# Extrudrboard.net
KiCad netlist of a schematic drawn in EAGLE
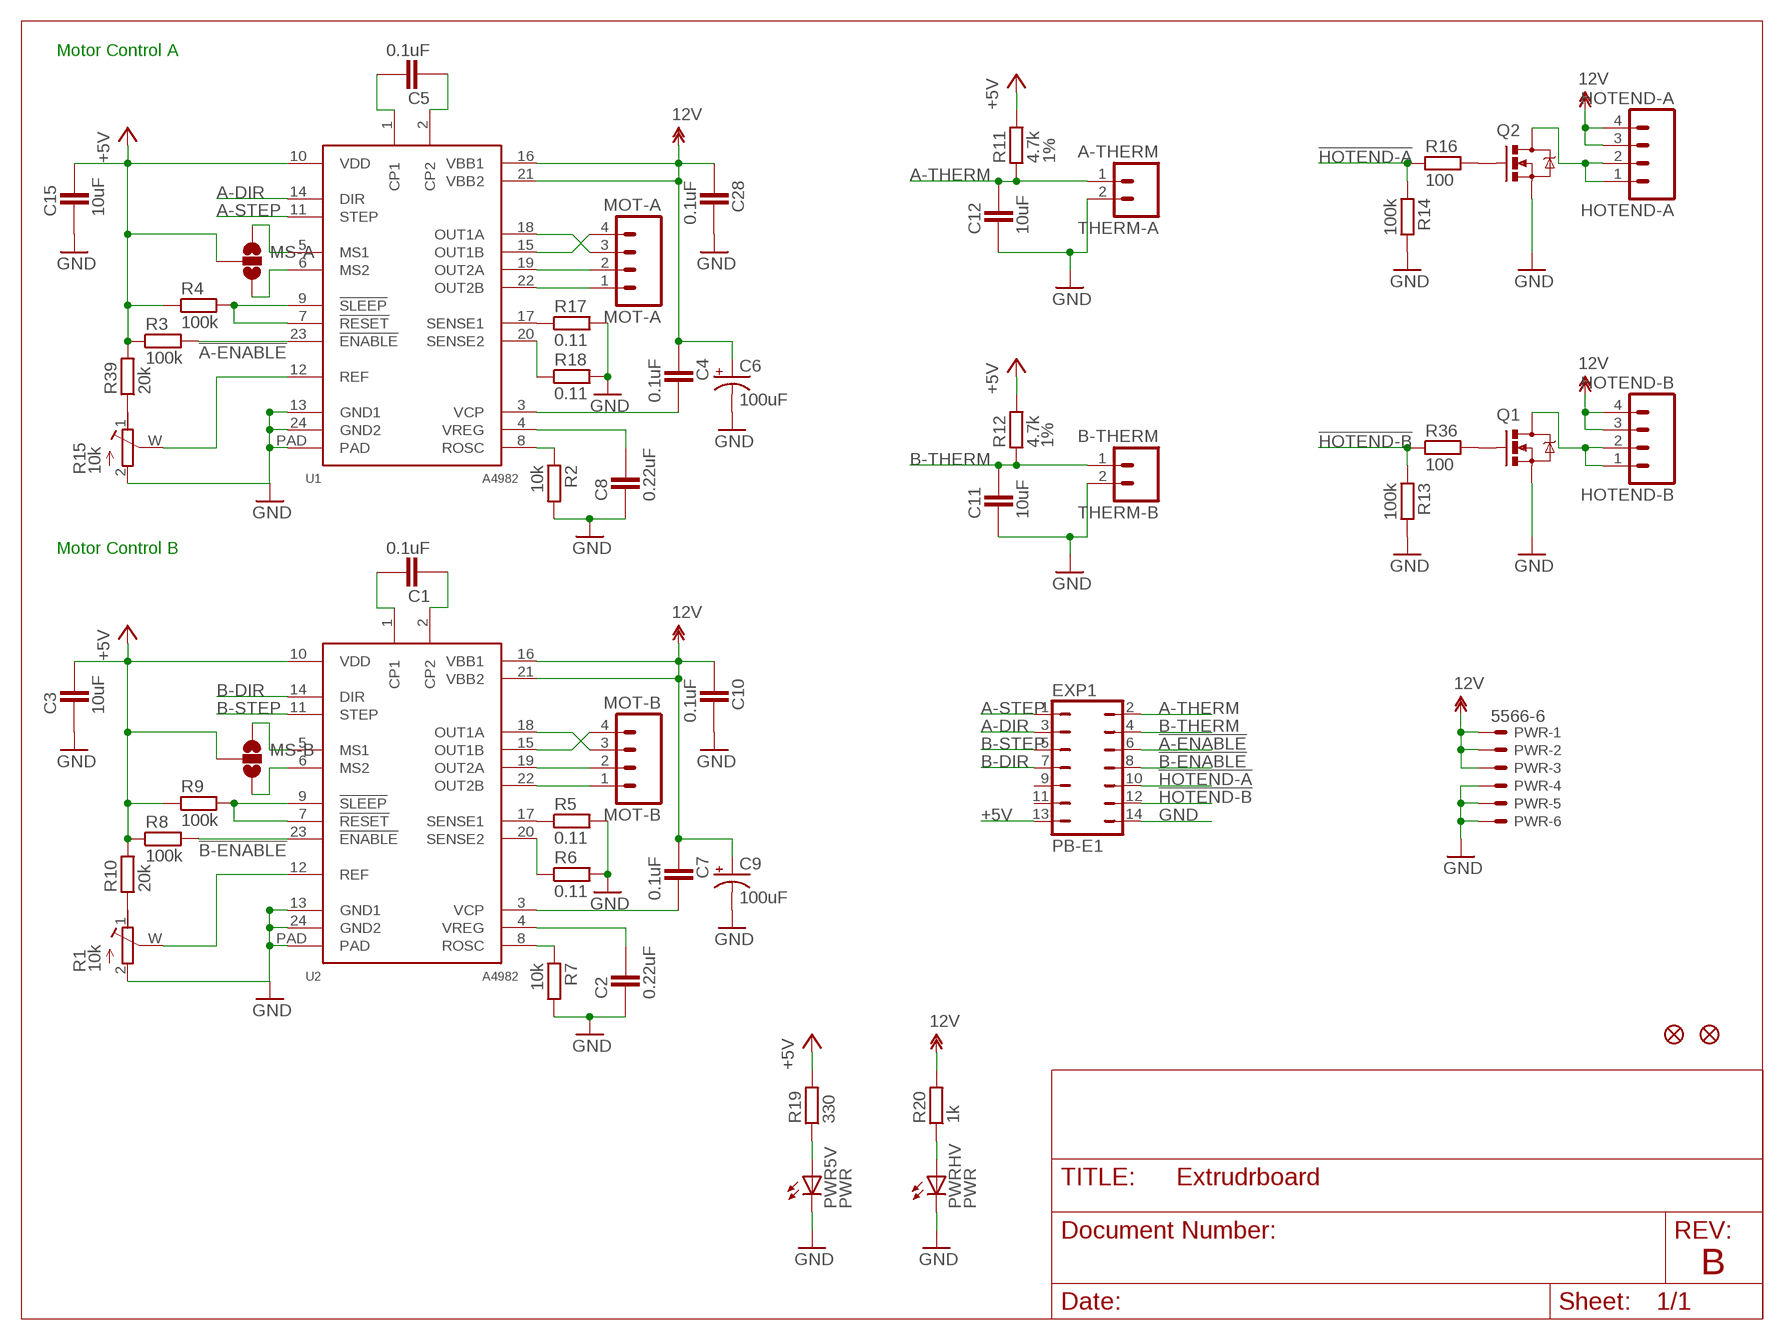
[diagram p0: schematic, sheet 1]

(export (version "E")
  (design (tool "Eeschema 10.0.6"))
  (components
    (comp (ref "C1")
      (value "0.1uF")
      (footprint "eagle-import:CAPC2012X145AN")
      (libsource (lib "eagle-import") (part "CAPACITOR_0805"))
    )
    (comp (ref "C2")
      (value "0.22uF")
      (footprint "eagle-import:CAPC2012X145AN")
      (libsource (lib "eagle-import") (part "CAPACITOR_0805"))
    )
    (comp (ref "C3")
      (value "10uF")
      (footprint "eagle-import:CAPC2012X145AN")
      (libsource (lib "eagle-import") (part "CAPACITOR_0805"))
    )
    (comp (ref "C4")
      (value "0.1uF")
      (footprint "eagle-import:CAPC2012X145AN")
      (libsource (lib "eagle-import") (part "CAPACITOR_0805"))
    )
    (comp (ref "C5")
      (value "0.1uF")
      (footprint "eagle-import:CAPC2012X145AN")
      (libsource (lib "eagle-import") (part "CAPACITOR_0805"))
    )
    (comp (ref "C6")
      (value "100uF")
      (footprint "eagle-import:PANASONIC_D")
      (libsource (lib "eagle-import") (part "CPOL-USD"))
    )
    (comp (ref "C7")
      (value "0.1uF")
      (footprint "eagle-import:CAPC2012X145AN")
      (libsource (lib "eagle-import") (part "CAPACITOR_0805"))
    )
    (comp (ref "C8")
      (value "0.22uF")
      (footprint "eagle-import:CAPC2012X145AN")
      (libsource (lib "eagle-import") (part "CAPACITOR_0805"))
    )
    (comp (ref "C9")
      (value "100uF")
      (footprint "eagle-import:PANASONIC_D")
      (libsource (lib "eagle-import") (part "CPOL-USD"))
    )
    (comp (ref "C10")
      (value "0.1uF")
      (footprint "eagle-import:CAPC2012X145AN")
      (libsource (lib "eagle-import") (part "CAPACITOR_0805"))
    )
    (comp (ref "C11")
      (value "10uF")
      (footprint "eagle-import:CAPC2012X145AN")
      (libsource (lib "eagle-import") (part "CAPACITOR_0805"))
    )
    (comp (ref "C12")
      (value "10uF")
      (footprint "eagle-import:CAPC2012X145AN")
      (libsource (lib "eagle-import") (part "CAPACITOR_0805"))
    )
    (comp (ref "C15")
      (value "10uF")
      (footprint "eagle-import:CAPC2012X145AN")
      (libsource (lib "eagle-import") (part "CAPACITOR_0805"))
    )
    (comp (ref "C28")
      (value "0.1uF")
      (footprint "eagle-import:CAPC2012X145AN")
      (libsource (lib "eagle-import") (part "CAPACITOR_0805"))
    )
    (comp (ref "EXP1")
      (value "PB-E1")
      (footprint "eagle-import:JP7Q")
      (libsource (lib "eagle-import") (part "JP7Q"))
    )
    (comp (ref "HOTEND-A")
      (value "HOTEND-A")
      (footprint "eagle-import:MOLEX-1X4")
      (libsource (lib "eagle-import") (part "M04POLAR"))
    )
    (comp (ref "HOTEND-B")
      (value "HOTEND-B")
      (footprint "eagle-import:MOLEX-1X4")
      (libsource (lib "eagle-import") (part "M04POLAR"))
    )
    (comp (ref "JP1")
      (value "FIDUCIAL1X2.5")
      (footprint "eagle-import:FIDUCIAL-1X2.5")
      (libsource (lib "eagle-import") (part "FIDUCIAL1X2.5"))
    )
    (comp (ref "JP2")
      (value "FIDUCIAL1X2.5")
      (footprint "eagle-import:FIDUCIAL-1X2.5")
      (libsource (lib "eagle-import") (part "FIDUCIAL1X2.5"))
    )
    (comp (ref "MOT-A")
      (value "MOT-A")
      (footprint "eagle-import:MOLEX-1X4")
      (libsource (lib "eagle-import") (part "M04POLAR"))
    )
    (comp (ref "MOT-B")
      (value "MOT-B")
      (footprint "eagle-import:MOLEX-1X4")
      (libsource (lib "eagle-import") (part "M04POLAR"))
    )
    (comp (ref "MS-A")
      (value "SOLDERJUMPER_2WAYCONNECTED")
      (footprint "eagle-import:SJ_3_CONNECTED")
      (libsource (lib "eagle-import") (part "SOLDERJUMPER_2WAYCONNECTED"))
    )
    (comp (ref "MS-B")
      (value "SOLDERJUMPER_2WAYCONNECTED")
      (footprint "eagle-import:SJ_3_CONNECTED")
      (libsource (lib "eagle-import") (part "SOLDERJUMPER_2WAYCONNECTED"))
    )
    (comp (ref "PWR")
      (value "5566-6")
      (footprint "eagle-import:5566-6")
      (fields (field (name "MPN") "95566-61002"))
      (libsource (lib "eagle-import") (part "5566-6"))
    )
    (comp (ref "PWR5V")
      (value "PWR")
      (footprint "eagle-import:CHIP-LED0805")
      (libsource (lib "eagle-import") (part "LEDCHIP-LED0805"))
    )
    (comp (ref "PWRHV")
      (value "PWR")
      (footprint "eagle-import:CHIP-LED0805")
      (libsource (lib "eagle-import") (part "LEDCHIP-LED0805"))
    )
    (comp (ref "Q1")
      (value "MOSFET-NCHANNELPTH2")
      (footprint "eagle-import:TO220V")
      (libsource (lib "eagle-import") (part "MOSFET-NCHANNELPTH2"))
    )
    (comp (ref "Q2")
      (value "MOSFET-NCHANNELPTH2")
      (footprint "eagle-import:TO220V")
      (libsource (lib "eagle-import") (part "MOSFET-NCHANNELPTH2"))
    )
    (comp (ref "R1")
      (value "10k")
      (footprint "eagle-import:RTRIM-ST4ETB")
      (libsource (lib "eagle-import") (part "RTRIM-ST-4EA"))
    )
    (comp (ref "R2")
      (value "10k")
      (footprint "eagle-import:RESC2012X70N")
      (libsource (lib "eagle-import") (part "RESISTOR_0805"))
    )
    (comp (ref "R3")
      (value "100k")
      (footprint "eagle-import:RESC2012X70N")
      (libsource (lib "eagle-import") (part "RESISTOR_0805"))
    )
    (comp (ref "R4")
      (value "100k")
      (footprint "eagle-import:RESC2012X70N")
      (libsource (lib "eagle-import") (part "RESISTOR_0805"))
    )
    (comp (ref "R5")
      (value "0.11")
      (footprint "eagle-import:RESC2012X70N")
      (libsource (lib "eagle-import") (part "RESISTOR_0805"))
    )
    (comp (ref "R6")
      (value "0.11")
      (footprint "eagle-import:RESC2012X70N")
      (libsource (lib "eagle-import") (part "RESISTOR_0805"))
    )
    (comp (ref "R7")
      (value "10k")
      (footprint "eagle-import:RESC2012X70N")
      (libsource (lib "eagle-import") (part "RESISTOR_0805"))
    )
    (comp (ref "R8")
      (value "100k")
      (footprint "eagle-import:RESC2012X70N")
      (libsource (lib "eagle-import") (part "RESISTOR_0805"))
    )
    (comp (ref "R9")
      (value "100k")
      (footprint "eagle-import:RESC2012X70N")
      (libsource (lib "eagle-import") (part "RESISTOR_0805"))
    )
    (comp (ref "R10")
      (value "20k")
      (footprint "eagle-import:RESC2012X70N")
      (libsource (lib "eagle-import") (part "RESISTOR_0805"))
    )
    (comp (ref "R11")
      (value "4.7k")
      (footprint "eagle-import:RESC2012X70N")
      (fields (field (name "TOLERANCE") "1%"))
      (libsource (lib "eagle-import") (part "RESISTOR_0805"))
    )
    (comp (ref "R12")
      (value "4.7k")
      (footprint "eagle-import:RESC2012X70N")
      (fields (field (name "TOLERANCE") "1%"))
      (libsource (lib "eagle-import") (part "RESISTOR_0805"))
    )
    (comp (ref "R13")
      (value "100k")
      (footprint "eagle-import:RESC2012X70N")
      (libsource (lib "eagle-import") (part "RESISTOR_0805"))
    )
    (comp (ref "R14")
      (value "100k")
      (footprint "eagle-import:RESC2012X70N")
      (libsource (lib "eagle-import") (part "RESISTOR_0805"))
    )
    (comp (ref "R15")
      (value "10k")
      (footprint "eagle-import:RTRIM-ST4ETB")
      (libsource (lib "eagle-import") (part "RTRIM-ST-4EA"))
    )
    (comp (ref "R16")
      (value "100")
      (footprint "eagle-import:RESC2012X70N")
      (libsource (lib "eagle-import") (part "RESISTOR_0805"))
    )
    (comp (ref "R17")
      (value "0.11")
      (footprint "eagle-import:RESC2012X70N")
      (libsource (lib "eagle-import") (part "RESISTOR_0805"))
    )
    (comp (ref "R18")
      (value "0.11")
      (footprint "eagle-import:RESC2012X70N")
      (libsource (lib "eagle-import") (part "RESISTOR_0805"))
    )
    (comp (ref "R19")
      (value "330")
      (footprint "eagle-import:RESC2012X70N")
      (libsource (lib "eagle-import") (part "RESISTOR_0805"))
    )
    (comp (ref "R20")
      (value "1k")
      (footprint "eagle-import:RESC2012X70N")
      (libsource (lib "eagle-import") (part "RESISTOR_0805"))
    )
    (comp (ref "R36")
      (value "100")
      (footprint "eagle-import:RESC2012X70N")
      (libsource (lib "eagle-import") (part "RESISTOR_0805"))
    )
    (comp (ref "R39")
      (value "20k")
      (footprint "eagle-import:RESC2012X70N")
      (libsource (lib "eagle-import") (part "RESISTOR_0805"))
    )
    (comp (ref "THERM-A")
      (value "A-THERM")
      (footprint "eagle-import:1X02")
      (libsource (lib "eagle-import") (part "M02PTH"))
    )
    (comp (ref "THERM-B")
      (value "B-THERM")
      (footprint "eagle-import:1X02")
      (libsource (lib "eagle-import") (part "M02PTH"))
    )
    (comp (ref "U1")
      (value "A4982")
      (footprint "eagle-import:TSSOP-24")
      (libsource (lib "eagle-import") (part "A4982"))
    )
    (comp (ref "U2")
      (value "A4982")
      (footprint "eagle-import:TSSOP-24")
      (libsource (lib "eagle-import") (part "A4982"))
    )
  )
  (nets
    (net (code "1") (name "+5V") (class "Default")
      (node (ref "C15") (pin "2") (pinfunction "2_2") (pintype "passive"))
      (node (ref "C3") (pin "2") (pinfunction "2_2") (pintype "passive"))
      (node (ref "EXP1") (pin "13") (pinfunction "13_13") (pintype "passive"))
      (node (ref "MS-A") (pin "2") (pinfunction "2_2") (pintype "passive"))
      (node (ref "MS-B") (pin "2") (pinfunction "2_2") (pintype "passive"))
      (node (ref "R10") (pin "2") (pinfunction "2_2") (pintype "passive"))
      (node (ref "R11") (pin "2") (pinfunction "2_2") (pintype "passive"))
      (node (ref "R12") (pin "2") (pinfunction "2_2") (pintype "passive"))
      (node (ref "R19") (pin "2") (pinfunction "2_2") (pintype "passive"))
      (node (ref "R3") (pin "1") (pinfunction "1_1") (pintype "passive"))
      (node (ref "R39") (pin "2") (pinfunction "2_2") (pintype "passive"))
      (node (ref "R4") (pin "1") (pinfunction "1_1") (pintype "passive"))
      (node (ref "R8") (pin "1") (pinfunction "1_1") (pintype "passive"))
      (node (ref "R9") (pin "1") (pinfunction "1_1") (pintype "passive"))
      (node (ref "U1") (pin "10") (pinfunction "VDD_10") (pintype "power_in"))
      (node (ref "U2") (pin "10") (pinfunction "VDD_10") (pintype "power_in"))
    )
    (net (code "2") (name "/A-DIR") (class "Default")
      (node (ref "EXP1") (pin "3") (pinfunction "3_3") (pintype "passive"))
      (node (ref "U1") (pin "14") (pinfunction "DIR_14") (pintype "input"))
    )
    (net (code "3") (name "/A-STEP") (class "Default")
      (node (ref "EXP1") (pin "1") (pinfunction "1_1") (pintype "passive"))
      (node (ref "U1") (pin "11") (pinfunction "STEP_11") (pintype "input"))
    )
    (net (code "4") (name "/A-THERM") (class "Default")
      (node (ref "C12") (pin "2") (pinfunction "2_2") (pintype "passive"))
      (node (ref "EXP1") (pin "2") (pinfunction "2_2") (pintype "passive"))
      (node (ref "R11") (pin "1") (pinfunction "1_1") (pintype "passive"))
      (node (ref "THERM-A") (pin "1") (pinfunction "1_1") (pintype "passive"))
    )
    (net (code "5") (name "/B-DIR") (class "Default")
      (node (ref "EXP1") (pin "7") (pinfunction "7_7") (pintype "passive"))
      (node (ref "U2") (pin "14") (pinfunction "DIR_14") (pintype "input"))
    )
    (net (code "6") (name "/B-STEP") (class "Default")
      (node (ref "EXP1") (pin "5") (pinfunction "5_5") (pintype "passive"))
      (node (ref "U2") (pin "11") (pinfunction "STEP_11") (pintype "input"))
    )
    (net (code "7") (name "/B-THERM") (class "Default")
      (node (ref "C11") (pin "2") (pinfunction "2_2") (pintype "passive"))
      (node (ref "EXP1") (pin "4") (pinfunction "4_4") (pintype "passive"))
      (node (ref "R12") (pin "1") (pinfunction "1_1") (pintype "passive"))
      (node (ref "THERM-B") (pin "1") (pinfunction "1_1") (pintype "passive"))
    )
    (net (code "8") (name "/~{A-ENABLE}") (class "Default")
      (node (ref "EXP1") (pin "6") (pinfunction "6_6") (pintype "passive"))
      (node (ref "R3") (pin "2") (pinfunction "2_2") (pintype "passive"))
      (node (ref "U1") (pin "23") (pinfunction "~{ENABLE}_23") (pintype "input"))
    )
    (net (code "9") (name "/~{B-ENABLE}") (class "Default")
      (node (ref "EXP1") (pin "8") (pinfunction "8_8") (pintype "passive"))
      (node (ref "R8") (pin "2") (pinfunction "2_2") (pintype "passive"))
      (node (ref "U2") (pin "23") (pinfunction "~{ENABLE}_23") (pintype "input"))
    )
    (net (code "10") (name "/~{HOTEND-A}") (class "Default")
      (node (ref "EXP1") (pin "10") (pinfunction "10_10") (pintype "passive"))
      (node (ref "R14") (pin "1") (pinfunction "1_1") (pintype "passive"))
      (node (ref "R16") (pin "1") (pinfunction "1_1") (pintype "passive"))
    )
    (net (code "11") (name "/~{HOTEND-B}") (class "Default")
      (node (ref "EXP1") (pin "12") (pinfunction "12_12") (pintype "passive"))
      (node (ref "R13") (pin "1") (pinfunction "1_1") (pintype "passive"))
      (node (ref "R36") (pin "1") (pinfunction "1_1") (pintype "passive"))
    )
    (net (code "12") (name "12V") (class "Default")
      (node (ref "C10") (pin "1") (pinfunction "1_1") (pintype "passive"))
      (node (ref "C28") (pin "1") (pinfunction "1_1") (pintype "passive"))
      (node (ref "C4") (pin "1") (pinfunction "1_1") (pintype "passive"))
      (node (ref "C6") (pin "+") (pinfunction "+_+") (pintype "passive"))
      (node (ref "C7") (pin "1") (pinfunction "1_1") (pintype "passive"))
      (node (ref "C9") (pin "+") (pinfunction "+_+") (pintype "passive"))
      (node (ref "HOTEND-A") (pin "3") (pinfunction "3_3") (pintype "passive"))
      (node (ref "HOTEND-A") (pin "4") (pinfunction "4_4") (pintype "passive"))
      (node (ref "HOTEND-B") (pin "3") (pinfunction "3_3") (pintype "passive"))
      (node (ref "HOTEND-B") (pin "4") (pinfunction "4_4") (pintype "passive"))
      (node (ref "PWR") (pin "1") (pinfunction "S_1") (pintype "passive"))
      (node (ref "PWR") (pin "2") (pinfunction "S_2") (pintype "passive"))
      (node (ref "PWR") (pin "3") (pinfunction "S_3") (pintype "passive"))
      (node (ref "R20") (pin "2") (pinfunction "2_2") (pintype "passive"))
      (node (ref "U1") (pin "16") (pinfunction "VBB1_16") (pintype "power_in"))
      (node (ref "U1") (pin "21") (pinfunction "VBB2_21") (pintype "power_in"))
      (node (ref "U2") (pin "16") (pinfunction "VBB1_16") (pintype "power_in"))
      (node (ref "U2") (pin "21") (pinfunction "VBB2_21") (pintype "power_in"))
    )
    (net (code "13") (name "GND") (class "Default")
      (node (ref "C10") (pin "2") (pinfunction "2_2") (pintype "passive"))
      (node (ref "C11") (pin "1") (pinfunction "1_1") (pintype "passive"))
      (node (ref "C12") (pin "1") (pinfunction "1_1") (pintype "passive"))
      (node (ref "C15") (pin "1") (pinfunction "1_1") (pintype "passive"))
      (node (ref "C2") (pin "1") (pinfunction "1_1") (pintype "passive"))
      (node (ref "C28") (pin "2") (pinfunction "2_2") (pintype "passive"))
      (node (ref "C3") (pin "1") (pinfunction "1_1") (pintype "passive"))
      (node (ref "C6") (pin "-") (pinfunction "-_-") (pintype "passive"))
      (node (ref "C8") (pin "1") (pinfunction "1_1") (pintype "passive"))
      (node (ref "C9") (pin "-") (pinfunction "-_-") (pintype "passive"))
      (node (ref "EXP1") (pin "14") (pinfunction "14_14") (pintype "passive"))
      (node (ref "PWR") (pin "4") (pinfunction "S_4") (pintype "passive"))
      (node (ref "PWR") (pin "5") (pinfunction "S_5") (pintype "passive"))
      (node (ref "PWR") (pin "6") (pinfunction "S_6") (pintype "passive"))
      (node (ref "PWR5V") (pin "C") (pinfunction "C_C") (pintype "passive"))
      (node (ref "PWRHV") (pin "C") (pinfunction "C_C") (pintype "passive"))
      (node (ref "Q1") (pin "3") (pinfunction "S_3") (pintype "passive"))
      (node (ref "Q2") (pin "3") (pinfunction "S_3") (pintype "passive"))
      (node (ref "R1") (pin "2") (pinfunction "E_2") (pintype "passive"))
      (node (ref "R13") (pin "2") (pinfunction "2_2") (pintype "passive"))
      (node (ref "R14") (pin "2") (pinfunction "2_2") (pintype "passive"))
      (node (ref "R15") (pin "2") (pinfunction "E_2") (pintype "passive"))
      (node (ref "R17") (pin "2") (pinfunction "2_2") (pintype "passive"))
      (node (ref "R18") (pin "2") (pinfunction "2_2") (pintype "passive"))
      (node (ref "R2") (pin "2") (pinfunction "2_2") (pintype "passive"))
      (node (ref "R5") (pin "2") (pinfunction "2_2") (pintype "passive"))
      (node (ref "R6") (pin "2") (pinfunction "2_2") (pintype "passive"))
      (node (ref "R7") (pin "2") (pinfunction "2_2") (pintype "passive"))
      (node (ref "THERM-A") (pin "2") (pinfunction "2_2") (pintype "passive"))
      (node (ref "THERM-B") (pin "2") (pinfunction "2_2") (pintype "passive"))
      (node (ref "U1") (pin "13") (pinfunction "GND1_13") (pintype "power_in"))
      (node (ref "U1") (pin "24") (pinfunction "GND2_24") (pintype "power_in"))
      (node (ref "U1") (pin "PAD") (pinfunction "PAD_PAD") (pintype "power_in"))
      (node (ref "U2") (pin "13") (pinfunction "GND1_13") (pintype "power_in"))
      (node (ref "U2") (pin "24") (pinfunction "GND2_24") (pintype "power_in"))
      (node (ref "U2") (pin "PAD") (pinfunction "PAD_PAD") (pintype "power_in"))
    )
    (net (code "14") (name "Net-(PWR5V-PadA)") (class "Default")
      (node (ref "PWR5V") (pin "A") (pinfunction "A_A") (pintype "passive"))
      (node (ref "R19") (pin "1") (pinfunction "1_1") (pintype "passive"))
    )
    (net (code "15") (name "Net-(PWRHV-PadA)") (class "Default")
      (node (ref "PWRHV") (pin "A") (pinfunction "A_A") (pintype "passive"))
      (node (ref "R20") (pin "1") (pinfunction "1_1") (pintype "passive"))
    )
    (net (code "16") (name "Net-(Q1-D)") (class "Default")
      (node (ref "HOTEND-B") (pin "1") (pinfunction "1_1") (pintype "passive"))
      (node (ref "HOTEND-B") (pin "2") (pinfunction "2_2") (pintype "passive"))
      (node (ref "Q1") (pin "2") (pinfunction "D_2") (pintype "passive"))
    )
    (net (code "17") (name "Net-(Q1-G)") (class "Default")
      (node (ref "Q1") (pin "1") (pinfunction "G_1") (pintype "passive"))
      (node (ref "R36") (pin "2") (pinfunction "2_2") (pintype "passive"))
    )
    (net (code "18") (name "Net-(Q2-D)") (class "Default")
      (node (ref "HOTEND-A") (pin "1") (pinfunction "1_1") (pintype "passive"))
      (node (ref "HOTEND-A") (pin "2") (pinfunction "2_2") (pintype "passive"))
      (node (ref "Q2") (pin "2") (pinfunction "D_2") (pintype "passive"))
    )
    (net (code "19") (name "Net-(Q2-G)") (class "Default")
      (node (ref "Q2") (pin "1") (pinfunction "G_1") (pintype "passive"))
      (node (ref "R16") (pin "2") (pinfunction "2_2") (pintype "passive"))
    )
    (net (code "20") (name "Net-(R1-A)") (class "Default")
      (node (ref "R1") (pin "1") (pinfunction "A_1") (pintype "passive"))
      (node (ref "R10") (pin "1") (pinfunction "1_1") (pintype "passive"))
    )
    (net (code "21") (name "Net-(R1-S)") (class "Default")
      (node (ref "R1") (pin "W") (pinfunction "S_W") (pintype "passive"))
      (node (ref "U2") (pin "12") (pinfunction "REF_12") (pintype "input"))
    )
    (net (code "22") (name "Net-(R15-A)") (class "Default")
      (node (ref "R15") (pin "1") (pinfunction "A_1") (pintype "passive"))
      (node (ref "R39") (pin "1") (pinfunction "1_1") (pintype "passive"))
    )
    (net (code "23") (name "Net-(R15-S)") (class "Default")
      (node (ref "R15") (pin "W") (pinfunction "S_W") (pintype "passive"))
      (node (ref "U1") (pin "12") (pinfunction "REF_12") (pintype "input"))
    )
    (net (code "24") (name "Net-(U1-CP1)") (class "Default")
      (node (ref "C5") (pin "2") (pinfunction "2_2") (pintype "passive"))
      (node (ref "U1") (pin "1") (pinfunction "CP1_1") (pintype "passive"))
    )
    (net (code "25") (name "Net-(U1-CP2)") (class "Default")
      (node (ref "C5") (pin "1") (pinfunction "1_1") (pintype "passive"))
      (node (ref "U1") (pin "2") (pinfunction "CP2_2") (pintype "passive"))
    )
    (net (code "26") (name "Net-(U1-MS1)") (class "Default")
      (node (ref "MS-A") (pin "1") (pinfunction "1_1") (pintype "passive"))
      (node (ref "U1") (pin "5") (pinfunction "MS1_5") (pintype "input"))
    )
    (net (code "27") (name "Net-(U1-MS2)") (class "Default")
      (node (ref "MS-A") (pin "3") (pinfunction "3_3") (pintype "passive"))
      (node (ref "U1") (pin "6") (pinfunction "MS2_6") (pintype "input"))
    )
    (net (code "28") (name "Net-(U1-OUT1A)") (class "Default")
      (node (ref "MOT-A") (pin "3") (pinfunction "3_3") (pintype "passive"))
      (node (ref "U1") (pin "18") (pinfunction "OUT1A_18") (pintype "output"))
    )
    (net (code "29") (name "Net-(U1-OUT1B)") (class "Default")
      (node (ref "MOT-A") (pin "4") (pinfunction "4_4") (pintype "passive"))
      (node (ref "U1") (pin "15") (pinfunction "OUT1B_15") (pintype "output"))
    )
    (net (code "30") (name "Net-(U1-OUT2A)") (class "Default")
      (node (ref "MOT-A") (pin "2") (pinfunction "2_2") (pintype "passive"))
      (node (ref "U1") (pin "19") (pinfunction "OUT2A_19") (pintype "output"))
    )
    (net (code "31") (name "Net-(U1-OUT2B)") (class "Default")
      (node (ref "MOT-A") (pin "1") (pinfunction "1_1") (pintype "passive"))
      (node (ref "U1") (pin "22") (pinfunction "OUT2B_22") (pintype "output"))
    )
    (net (code "32") (name "Net-(U1-ROSC)") (class "Default")
      (node (ref "R2") (pin "1") (pinfunction "1_1") (pintype "passive"))
      (node (ref "U1") (pin "8") (pinfunction "ROSC_8") (pintype "passive"))
    )
    (net (code "33") (name "Net-(U1-SENSE1)") (class "Default")
      (node (ref "R17") (pin "1") (pinfunction "1_1") (pintype "passive"))
      (node (ref "U1") (pin "17") (pinfunction "SENSE1_17") (pintype "passive"))
    )
    (net (code "34") (name "Net-(U1-SENSE2)") (class "Default")
      (node (ref "R18") (pin "1") (pinfunction "1_1") (pintype "passive"))
      (node (ref "U1") (pin "20") (pinfunction "SENSE2_20") (pintype "passive"))
    )
    (net (code "35") (name "Net-(U1-VCP)") (class "Default")
      (node (ref "C4") (pin "2") (pinfunction "2_2") (pintype "passive"))
      (node (ref "U1") (pin "3") (pinfunction "VCP_3") (pintype "passive"))
    )
    (net (code "36") (name "Net-(U1-VREG)") (class "Default")
      (node (ref "C8") (pin "2") (pinfunction "2_2") (pintype "passive"))
      (node (ref "U1") (pin "4") (pinfunction "VREG_4") (pintype "passive"))
    )
    (net (code "37") (name "Net-(U1-~{RESET})") (class "Default")
      (node (ref "R4") (pin "2") (pinfunction "2_2") (pintype "passive"))
      (node (ref "U1") (pin "7") (pinfunction "~{RESET}_7") (pintype "input"))
      (node (ref "U1") (pin "9") (pinfunction "~{SLEEP}_9") (pintype "input"))
    )
    (net (code "38") (name "Net-(U2-CP1)") (class "Default")
      (node (ref "C1") (pin "2") (pinfunction "2_2") (pintype "passive"))
      (node (ref "U2") (pin "1") (pinfunction "CP1_1") (pintype "passive"))
    )
    (net (code "39") (name "Net-(U2-CP2)") (class "Default")
      (node (ref "C1") (pin "1") (pinfunction "1_1") (pintype "passive"))
      (node (ref "U2") (pin "2") (pinfunction "CP2_2") (pintype "passive"))
    )
    (net (code "40") (name "Net-(U2-MS1)") (class "Default")
      (node (ref "MS-B") (pin "1") (pinfunction "1_1") (pintype "passive"))
      (node (ref "U2") (pin "5") (pinfunction "MS1_5") (pintype "input"))
    )
    (net (code "41") (name "Net-(U2-MS2)") (class "Default")
      (node (ref "MS-B") (pin "3") (pinfunction "3_3") (pintype "passive"))
      (node (ref "U2") (pin "6") (pinfunction "MS2_6") (pintype "input"))
    )
    (net (code "42") (name "Net-(U2-OUT1A)") (class "Default")
      (node (ref "MOT-B") (pin "3") (pinfunction "3_3") (pintype "passive"))
      (node (ref "U2") (pin "18") (pinfunction "OUT1A_18") (pintype "output"))
    )
    (net (code "43") (name "Net-(U2-OUT1B)") (class "Default")
      (node (ref "MOT-B") (pin "4") (pinfunction "4_4") (pintype "passive"))
      (node (ref "U2") (pin "15") (pinfunction "OUT1B_15") (pintype "output"))
    )
    (net (code "44") (name "Net-(U2-OUT2A)") (class "Default")
      (node (ref "MOT-B") (pin "2") (pinfunction "2_2") (pintype "passive"))
      (node (ref "U2") (pin "19") (pinfunction "OUT2A_19") (pintype "output"))
    )
    (net (code "45") (name "Net-(U2-OUT2B)") (class "Default")
      (node (ref "MOT-B") (pin "1") (pinfunction "1_1") (pintype "passive"))
      (node (ref "U2") (pin "22") (pinfunction "OUT2B_22") (pintype "output"))
    )
    (net (code "46") (name "Net-(U2-ROSC)") (class "Default")
      (node (ref "R7") (pin "1") (pinfunction "1_1") (pintype "passive"))
      (node (ref "U2") (pin "8") (pinfunction "ROSC_8") (pintype "passive"))
    )
    (net (code "47") (name "Net-(U2-SENSE1)") (class "Default")
      (node (ref "R5") (pin "1") (pinfunction "1_1") (pintype "passive"))
      (node (ref "U2") (pin "17") (pinfunction "SENSE1_17") (pintype "passive"))
    )
    (net (code "48") (name "Net-(U2-SENSE2)") (class "Default")
      (node (ref "R6") (pin "1") (pinfunction "1_1") (pintype "passive"))
      (node (ref "U2") (pin "20") (pinfunction "SENSE2_20") (pintype "passive"))
    )
    (net (code "49") (name "Net-(U2-VCP)") (class "Default")
      (node (ref "C7") (pin "2") (pinfunction "2_2") (pintype "passive"))
      (node (ref "U2") (pin "3") (pinfunction "VCP_3") (pintype "passive"))
    )
    (net (code "50") (name "Net-(U2-VREG)") (class "Default")
      (node (ref "C2") (pin "2") (pinfunction "2_2") (pintype "passive"))
      (node (ref "U2") (pin "4") (pinfunction "VREG_4") (pintype "passive"))
    )
    (net (code "51") (name "Net-(U2-~{RESET})") (class "Default")
      (node (ref "R9") (pin "2") (pinfunction "2_2") (pintype "passive"))
      (node (ref "U2") (pin "7") (pinfunction "~{RESET}_7") (pintype "input"))
      (node (ref "U2") (pin "9") (pinfunction "~{SLEEP}_9") (pintype "input"))
    )
    (net (code "52") (name "unconnected-(EXP1-Pad9)") (class "Default")
      (node (ref "EXP1") (pin "9") (pinfunction "9_9") (pintype "passive"))
    )
    (net (code "53") (name "unconnected-(EXP1-Pad11)") (class "Default")
      (node (ref "EXP1") (pin "11") (pinfunction "11_11") (pintype "passive"))
    )
  )
)
